# BradLightFlash_rev2.net
KiCad netlist of a schematic drawn in EAGLE
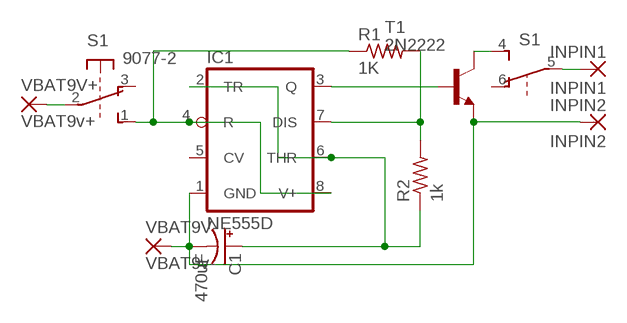
[diagram p0: schematic, sheet 1]

(export (version "E")
  (design (tool "Eeschema 10.0.6"))
  (components
    (comp (ref "C1")
      (value "470uF")
      (footprint "eagle-import:E2,5-6")
      (libsource (lib "eagle-import") (part "CPOL-USE2.5-6"))
    )
    (comp (ref "IC1")
      (value "NE555D")
      (footprint "eagle-import:SO08")
      (libsource (lib "eagle-import") (part "555DNE"))
    )
    (comp (ref "INPIN1")
      (value "INPIN1")
      (footprint "eagle-import:2,54_1,1")
      (libsource (lib "eagle-import") (part "2,54/1,1"))
    )
    (comp (ref "INPIN2")
      (value "INPIN2")
      (footprint "eagle-import:2,54_1,1")
      (libsource (lib "eagle-import") (part "2,54/1,1"))
    )
    (comp (ref "R1")
      (value "1K")
      (footprint "eagle-import:0309V")
      (libsource (lib "eagle-import") (part "R-US_0309/V"))
    )
    (comp (ref "R2")
      (value "1k")
      (footprint "eagle-import:0309V")
      (libsource (lib "eagle-import") (part "R-US_0309/V"))
    )
    (comp (ref "S1")
      (value "9077-2")
      (footprint "eagle-import:9077-2")
      (libsource (lib "eagle-import") (part "9077-2"))
    )
    (comp (ref "T1")
      (value "2N2222")
      (footprint "eagle-import:TO92-EBC-OVAL")
      (libsource (lib "eagle-import") (part "2N2222"))
    )
    (comp (ref "VBAT9V+")
      (value "VBAT9v+")
      (footprint "eagle-import:2,54_1,1")
      (libsource (lib "eagle-import") (part "2,54/1,1"))
    )
    (comp (ref "VBAT9V-")
      (value "VBAT9v-")
      (footprint "eagle-import:2,54_1,1")
      (libsource (lib "eagle-import") (part "2,54/1,1"))
    )
  )
  (nets
    (net (code "1") (name "Net-(IC1-DIS)") (class "Default")
      (node (ref "IC1") (pin "7") (pinfunction "DIS_7") (pintype "input"))
      (node (ref "R1") (pin "2") (pinfunction "2_2") (pintype "passive"))
      (node (ref "R2") (pin "2") (pinfunction "2_2") (pintype "passive"))
    )
    (net (code "2") (name "Net-(IC1-GND)") (class "Default")
      (node (ref "C1") (pin "-") (pinfunction "-_-") (pintype "passive"))
      (node (ref "IC1") (pin "1") (pinfunction "GND_1") (pintype "power_in"))
      (node (ref "INPIN2") (pin "1") (pinfunction "P_1") (pintype "passive"))
      (node (ref "T1") (pin "E") (pinfunction "E_E") (pintype "passive"))
      (node (ref "VBAT9V-") (pin "1") (pinfunction "P_1") (pintype "passive"))
    )
    (net (code "3") (name "Net-(IC1-Q)") (class "Default")
      (node (ref "IC1") (pin "3") (pinfunction "Q_3") (pintype "output"))
      (node (ref "T1") (pin "B") (pinfunction "B_B") (pintype "passive"))
    )
    (net (code "4") (name "Net-(IC1-R)") (class "Default")
      (node (ref "IC1") (pin "4") (pinfunction "R_4") (pintype "input"))
      (node (ref "IC1") (pin "8") (pinfunction "V+_8") (pintype "power_in"))
      (node (ref "R1") (pin "1") (pinfunction "1_1") (pintype "passive"))
      (node (ref "S1") (pin "1") (pinfunction "S_1") (pintype "passive"))
    )
    (net (code "5") (name "Net-(IC1-THR)") (class "Default")
      (node (ref "C1") (pin "+") (pinfunction "+_+") (pintype "passive"))
      (node (ref "IC1") (pin "2") (pinfunction "TR_2") (pintype "input"))
      (node (ref "IC1") (pin "6") (pinfunction "THR_6") (pintype "input"))
      (node (ref "R2") (pin "1") (pinfunction "1_1") (pintype "passive"))
    )
    (net (code "6") (name "Net-(INPIN1-P)") (class "Default")
      (node (ref "INPIN1") (pin "1") (pinfunction "P_1") (pintype "passive"))
      (node (ref "S1") (pin "5") (pinfunction "P_5") (pintype "passive"))
    )
    (net (code "7") (name "Net-(S1A-P)") (class "Default")
      (node (ref "S1") (pin "2") (pinfunction "P_2") (pintype "passive"))
      (node (ref "VBAT9V+") (pin "1") (pinfunction "P_1") (pintype "passive"))
    )
    (net (code "8") (name "Net-(S1B-S)") (class "Default")
      (node (ref "S1") (pin "4") (pinfunction "S_4") (pintype "passive"))
      (node (ref "T1") (pin "C") (pinfunction "C_C") (pintype "passive"))
    )
    (net (code "9") (name "unconnected-(IC1-CV-Pad5)") (class "Default")
      (node (ref "IC1") (pin "5") (pinfunction "CV_5") (pintype "input"))
    )
    (net (code "10") (name "unconnected-(S1A-O-Pad3)") (class "Default")
      (node (ref "S1") (pin "3") (pinfunction "O_3") (pintype "passive"))
    )
    (net (code "11") (name "unconnected-(S1B-O-Pad6)") (class "Default")
      (node (ref "S1") (pin "6") (pinfunction "O_6") (pintype "passive"))
    )
  )
)
